# gpxtendo.net
KiCad netlist of a schematic drawn in EAGLE
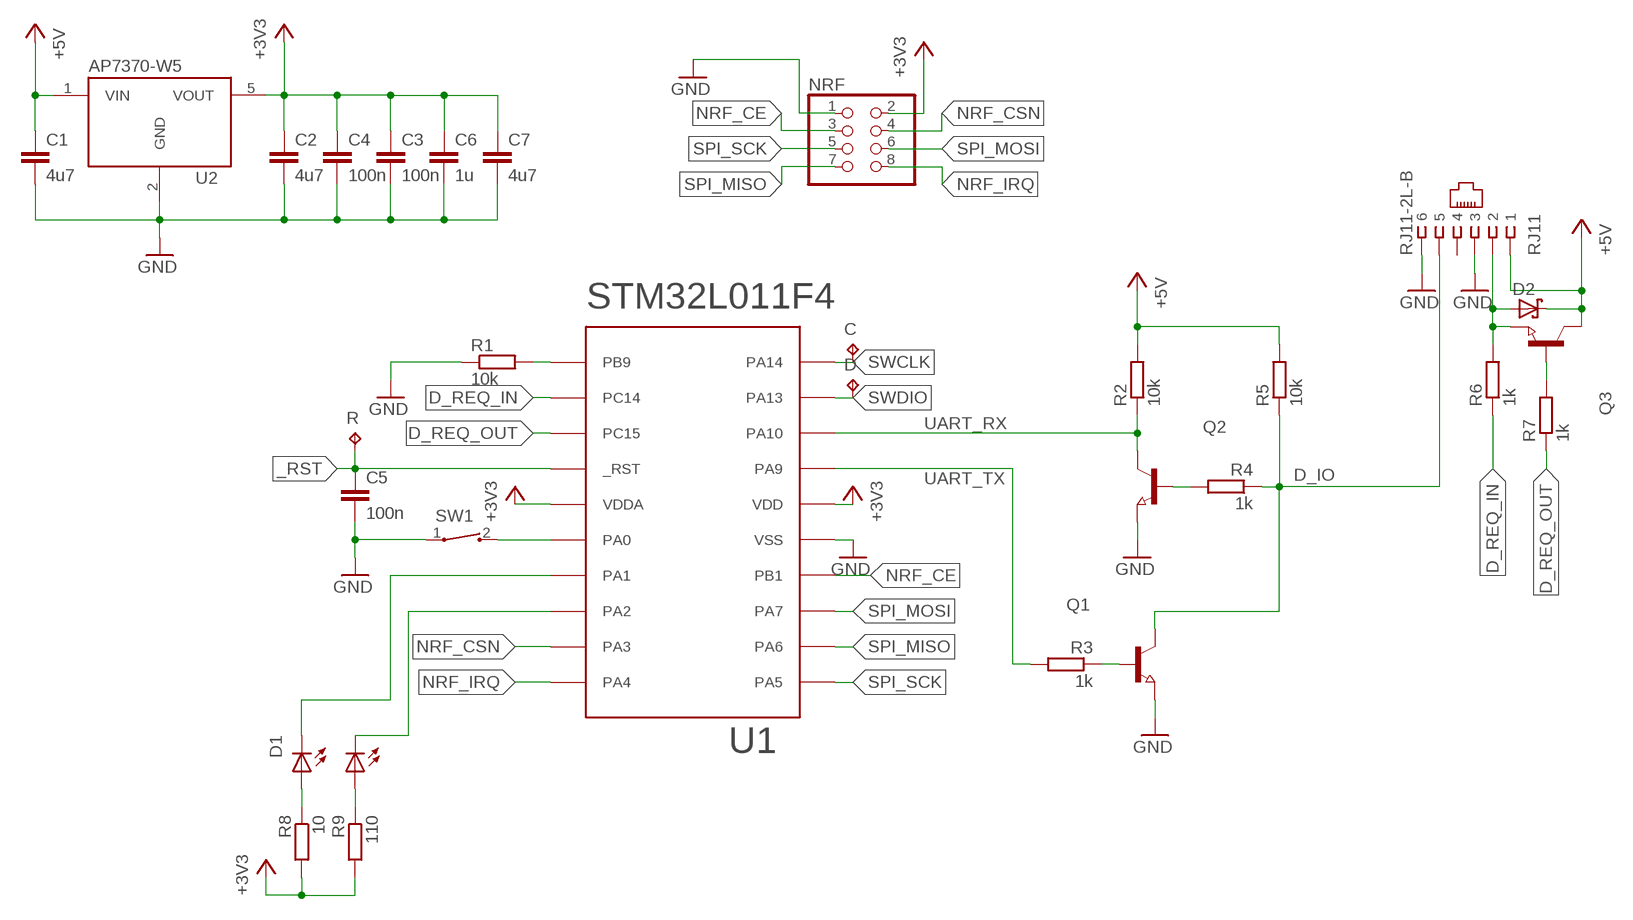
[diagram p0: schematic, sheet 1]

(export (version "E")
  (design (tool "Eeschema 10.0.6"))
  (components
    (comp (ref "C")
      (value "TPTP10R")
      (footprint "eagle-import:TP10R")
      (libsource (lib "eagle-import") (part "TPTP10R"))
    )
    (comp (ref "C1")
      (value "4u7")
      (footprint "eagle-import:C0603-S")
      (libsource (lib "eagle-import") (part "C0603-S"))
    )
    (comp (ref "C2")
      (value "4u7")
      (footprint "eagle-import:C0603-S")
      (libsource (lib "eagle-import") (part "C0603-S"))
    )
    (comp (ref "C3")
      (value "100n")
      (footprint "eagle-import:C0603-S")
      (libsource (lib "eagle-import") (part "C0603-S"))
    )
    (comp (ref "C4")
      (value "100n")
      (footprint "eagle-import:C0603-S")
      (libsource (lib "eagle-import") (part "C0603-S"))
    )
    (comp (ref "C5")
      (value "100n")
      (footprint "eagle-import:C0603-S")
      (libsource (lib "eagle-import") (part "C0603-S"))
    )
    (comp (ref "C6")
      (value "1u")
      (footprint "eagle-import:C0603-S")
      (libsource (lib "eagle-import") (part "C0603-S"))
    )
    (comp (ref "C7")
      (value "4u7")
      (footprint "eagle-import:C0603-S")
      (libsource (lib "eagle-import") (part "C0603-S"))
    )
    (comp (ref "D")
      (value "TPTP10R")
      (footprint "eagle-import:TP10R")
      (libsource (lib "eagle-import") (part "TPTP10R"))
    )
    (comp (ref "D1")
      (value "LED-DUAL")
      (footprint "eagle-import:LED-1210")
      (libsource (lib "eagle-import") (part "LED-DUAL"))
    )
    (comp (ref "D2")
      (value "PMEG4030")
      (footprint "eagle-import:SOD123")
      (libsource (lib "eagle-import") (part "PMEG4030"))
    )
    (comp (ref "NRF")
      (value "PINHD-2X4")
      (footprint "eagle-import:2X04")
      (libsource (lib "eagle-import") (part "PINHD-2X4"))
    )
    (comp (ref "Q1")
      (value "NPN-TRANSISTOR_SOT23")
      (footprint "eagle-import:SOT23")
      (libsource (lib "eagle-import") (part "NPN-TRANSISTOR_SOT23"))
    )
    (comp (ref "Q2")
      (value "NPN-TRANSISTOR_SOT23")
      (footprint "eagle-import:SOT23")
      (libsource (lib "eagle-import") (part "NPN-TRANSISTOR_SOT23"))
    )
    (comp (ref "Q3")
      (value "NPN-TRANSISTOR_SOT23")
      (footprint "eagle-import:SOT23")
      (libsource (lib "eagle-import") (part "NPN-TRANSISTOR_SOT23"))
    )
    (comp (ref "R")
      (value "TPTP10R")
      (footprint "eagle-import:TP10R")
      (libsource (lib "eagle-import") (part "TPTP10R"))
    )
    (comp (ref "R1")
      (value "10k")
      (footprint "eagle-import:R0603-S")
      (libsource (lib "eagle-import") (part "R0603-S"))
    )
    (comp (ref "R2")
      (value "10k")
      (footprint "eagle-import:R0603-S")
      (libsource (lib "eagle-import") (part "R0603-S"))
    )
    (comp (ref "R3")
      (value "1k")
      (footprint "eagle-import:R0603-S")
      (libsource (lib "eagle-import") (part "R0603-S"))
    )
    (comp (ref "R4")
      (value "1k")
      (footprint "eagle-import:R0603-S")
      (libsource (lib "eagle-import") (part "R0603-S"))
    )
    (comp (ref "R5")
      (value "10k")
      (footprint "eagle-import:R0603-S")
      (libsource (lib "eagle-import") (part "R0603-S"))
    )
    (comp (ref "R6")
      (value "1k")
      (footprint "eagle-import:R0603-S")
      (libsource (lib "eagle-import") (part "R0603-S"))
    )
    (comp (ref "R7")
      (value "1k")
      (footprint "eagle-import:R0603-S")
      (libsource (lib "eagle-import") (part "R0603-S"))
    )
    (comp (ref "R8")
      (value "10")
      (footprint "eagle-import:R0603-S")
      (libsource (lib "eagle-import") (part "R0603-S"))
    )
    (comp (ref "R9")
      (value "110")
      (footprint "eagle-import:R0603-S")
      (libsource (lib "eagle-import") (part "R0603-S"))
    )
    (comp (ref "RJ11")
      (value "RJ11-2L-B")
      (footprint "eagle-import:RJ11-NO_SHIELD")
      (fields (field (name "MF") "TYCO ELECTRONICS"))
      (libsource (lib "eagle-import") (part "RJ11-2L-B"))
    )
    (comp (ref "SW1")
      (value "SW-SPST")
      (footprint "eagle-import:TL3330")
      (libsource (lib "eagle-import") (part "SW-SPST"))
    )
    (comp (ref "U1")
      (value "STM32L011F4PX")
      (footprint "eagle-import:TSSOP-20")
      (libsource (lib "eagle-import") (part "STM32L011F4PX"))
    )
    (comp (ref "U2")
      (value "AP7370-W5")
      (footprint "eagle-import:SOT23-5")
      (libsource (lib "eagle-import") (part "AP7370-W5"))
    )
  )
  (nets
    (net (code "1") (name "+3V3") (class "Default")
      (node (ref "C2") (pin "1") (pinfunction "1_1") (pintype "passive"))
      (node (ref "C3") (pin "1") (pinfunction "1_1") (pintype "passive"))
      (node (ref "C4") (pin "1") (pinfunction "1_1") (pintype "passive"))
      (node (ref "C6") (pin "1") (pinfunction "1_1") (pintype "passive"))
      (node (ref "C7") (pin "1") (pinfunction "1_1") (pintype "passive"))
      (node (ref "NRF") (pin "2") (pinfunction "2_2") (pintype "passive"))
      (node (ref "R8") (pin "2") (pinfunction "2_2") (pintype "passive"))
      (node (ref "R9") (pin "2") (pinfunction "2_2") (pintype "passive"))
      (node (ref "U1") (pin "P$16") (pinfunction "VDD_P$16") (pintype "power_in"))
      (node (ref "U1") (pin "P$5") (pinfunction "VDDA_P$5") (pintype "power_in"))
      (node (ref "U2") (pin "5") (pinfunction "VOUT_5") (pintype "bidirectional"))
    )
    (net (code "2") (name "+5V") (class "Default")
      (node (ref "C1") (pin "1") (pinfunction "1_1") (pintype "passive"))
      (node (ref "D2") (pin "C") (pinfunction "C_C") (pintype "passive"))
      (node (ref "Q3") (pin "3") (pinfunction "C_3") (pintype "passive"))
      (node (ref "R2") (pin "2") (pinfunction "2_2") (pintype "passive"))
      (node (ref "R5") (pin "2") (pinfunction "2_2") (pintype "passive"))
      (node (ref "RJ11") (pin "1") (pinfunction "1_1") (pintype "passive"))
      (node (ref "U2") (pin "1") (pinfunction "VIN_1") (pintype "bidirectional"))
    )
    (net (code "3") (name "/D_IO") (class "Default")
      (node (ref "Q1") (pin "3") (pinfunction "C_3") (pintype "passive"))
      (node (ref "R4") (pin "1") (pinfunction "1_1") (pintype "passive"))
      (node (ref "R5") (pin "1") (pinfunction "1_1") (pintype "passive"))
      (node (ref "RJ11") (pin "5") (pinfunction "5_5") (pintype "passive"))
    )
    (net (code "4") (name "/UART_RX") (class "Default")
      (node (ref "Q2") (pin "3") (pinfunction "C_3") (pintype "passive"))
      (node (ref "R2") (pin "1") (pinfunction "1_1") (pintype "passive"))
      (node (ref "U1") (pin "P$18") (pinfunction "PA10_P$18") (pintype "bidirectional"))
    )
    (net (code "5") (name "/UART_TX") (class "Default")
      (node (ref "R3") (pin "2") (pinfunction "2_2") (pintype "passive"))
      (node (ref "U1") (pin "P$17") (pinfunction "PA9_P$17") (pintype "bidirectional"))
    )
    (net (code "6") (name "D_REQ_IN") (class "Default")
      (node (ref "R6") (pin "1") (pinfunction "1_1") (pintype "passive"))
      (node (ref "U1") (pin "P$2") (pinfunction "PC14_P$2") (pintype "bidirectional"))
    )
    (net (code "7") (name "D_REQ_OUT") (class "Default")
      (node (ref "R7") (pin "1") (pinfunction "1_1") (pintype "passive"))
      (node (ref "U1") (pin "P$3") (pinfunction "PC15_P$3") (pintype "bidirectional"))
    )
    (net (code "8") (name "GND") (class "Default")
      (node (ref "C1") (pin "2") (pinfunction "2_2") (pintype "passive"))
      (node (ref "C2") (pin "2") (pinfunction "2_2") (pintype "passive"))
      (node (ref "C3") (pin "2") (pinfunction "2_2") (pintype "passive"))
      (node (ref "C4") (pin "2") (pinfunction "2_2") (pintype "passive"))
      (node (ref "C5") (pin "2") (pinfunction "2_2") (pintype "passive"))
      (node (ref "C6") (pin "2") (pinfunction "2_2") (pintype "passive"))
      (node (ref "C7") (pin "2") (pinfunction "2_2") (pintype "passive"))
      (node (ref "NRF") (pin "1") (pinfunction "1_1") (pintype "passive"))
      (node (ref "Q1") (pin "2") (pinfunction "E_2") (pintype "passive"))
      (node (ref "Q2") (pin "2") (pinfunction "E_2") (pintype "passive"))
      (node (ref "R1") (pin "1") (pinfunction "1_1") (pintype "passive"))
      (node (ref "RJ11") (pin "3") (pinfunction "3_3") (pintype "passive"))
      (node (ref "RJ11") (pin "6") (pinfunction "6_6") (pintype "passive"))
      (node (ref "SW1") (pin "1") (pinfunction "1_1") (pintype "passive"))
      (node (ref "U1") (pin "P$15") (pinfunction "VSS_P$15") (pintype "power_in"))
      (node (ref "U2") (pin "2") (pinfunction "GND_2") (pintype "bidirectional"))
    )
    (net (code "9") (name "NRF_CE") (class "Default")
      (node (ref "NRF") (pin "3") (pinfunction "3_3") (pintype "passive"))
      (node (ref "U1") (pin "P$14") (pinfunction "PB1_P$14") (pintype "bidirectional"))
    )
    (net (code "10") (name "NRF_CSN") (class "Default")
      (node (ref "NRF") (pin "4") (pinfunction "4_4") (pintype "passive"))
      (node (ref "U1") (pin "P$9") (pinfunction "PA3_P$9") (pintype "bidirectional"))
    )
    (net (code "11") (name "NRF_IRQ") (class "Default")
      (node (ref "NRF") (pin "8") (pinfunction "8_8") (pintype "passive"))
      (node (ref "U1") (pin "P$10") (pinfunction "PA4_P$10") (pintype "bidirectional"))
    )
    (net (code "12") (name "Net-(D1-A0)") (class "Default")
      (node (ref "D1") (pin "2") (pinfunction "A0_2") (pintype "passive"))
      (node (ref "R9") (pin "1") (pinfunction "1_1") (pintype "passive"))
    )
    (net (code "13") (name "Net-(D1-A1)") (class "Default")
      (node (ref "D1") (pin "4") (pinfunction "A1_4") (pintype "passive"))
      (node (ref "R8") (pin "1") (pinfunction "1_1") (pintype "passive"))
    )
    (net (code "14") (name "Net-(D1-C0)") (class "Default")
      (node (ref "D1") (pin "1") (pinfunction "C0_1") (pintype "passive"))
      (node (ref "U1") (pin "P$8") (pinfunction "PA2_P$8") (pintype "bidirectional"))
    )
    (net (code "15") (name "Net-(D1-C1)") (class "Default")
      (node (ref "D1") (pin "3") (pinfunction "C1_3") (pintype "passive"))
      (node (ref "U1") (pin "P$7") (pinfunction "PA1_P$7") (pintype "bidirectional"))
    )
    (net (code "16") (name "Net-(Q1-B)") (class "Default")
      (node (ref "Q1") (pin "1") (pinfunction "B_1") (pintype "passive"))
      (node (ref "R3") (pin "1") (pinfunction "1_1") (pintype "passive"))
    )
    (net (code "17") (name "Net-(Q2-B)") (class "Default")
      (node (ref "Q2") (pin "1") (pinfunction "B_1") (pintype "passive"))
      (node (ref "R4") (pin "2") (pinfunction "2_2") (pintype "passive"))
    )
    (net (code "18") (name "Net-(Q3-B)") (class "Default")
      (node (ref "Q3") (pin "1") (pinfunction "B_1") (pintype "passive"))
      (node (ref "R7") (pin "2") (pinfunction "2_2") (pintype "passive"))
    )
    (net (code "19") (name "Net-(Q3-E)") (class "Default")
      (node (ref "D2") (pin "A") (pinfunction "A_A") (pintype "passive"))
      (node (ref "Q3") (pin "2") (pinfunction "E_2") (pintype "passive"))
      (node (ref "R6") (pin "2") (pinfunction "2_2") (pintype "passive"))
      (node (ref "RJ11") (pin "2") (pinfunction "2_2") (pintype "passive"))
    )
    (net (code "20") (name "Net-(U1-PA0)") (class "Default")
      (node (ref "SW1") (pin "2") (pinfunction "2_2") (pintype "passive"))
      (node (ref "U1") (pin "P$6") (pinfunction "PA0_P$6") (pintype "bidirectional"))
    )
    (net (code "21") (name "Net-(U1-PB9)") (class "Default")
      (node (ref "R1") (pin "2") (pinfunction "2_2") (pintype "passive"))
      (node (ref "U1") (pin "P$1") (pinfunction "PB9_P$1") (pintype "bidirectional"))
    )
    (net (code "22") (name "SPI_MISO") (class "Default")
      (node (ref "NRF") (pin "7") (pinfunction "7_7") (pintype "passive"))
      (node (ref "U1") (pin "P$12") (pinfunction "PA6_P$12") (pintype "bidirectional"))
    )
    (net (code "23") (name "SPI_MOSI") (class "Default")
      (node (ref "NRF") (pin "6") (pinfunction "6_6") (pintype "passive"))
      (node (ref "U1") (pin "P$13") (pinfunction "PA7_P$13") (pintype "bidirectional"))
    )
    (net (code "24") (name "SPI_SCK") (class "Default")
      (node (ref "NRF") (pin "5") (pinfunction "5_5") (pintype "passive"))
      (node (ref "U1") (pin "P$11") (pinfunction "PA5_P$11") (pintype "bidirectional"))
    )
    (net (code "25") (name "SWCLK") (class "Default")
      (node (ref "C") (pin "TP") (pinfunction "TP_TP") (pintype "input"))
      (node (ref "U1") (pin "P$20") (pinfunction "PA14_P$20") (pintype "bidirectional"))
    )
    (net (code "26") (name "SWDIO") (class "Default")
      (node (ref "D") (pin "TP") (pinfunction "TP_TP") (pintype "input"))
      (node (ref "U1") (pin "P$19") (pinfunction "PA13_P$19") (pintype "bidirectional"))
    )
    (net (code "27") (name "_RST") (class "Default")
      (node (ref "C5") (pin "1") (pinfunction "1_1") (pintype "passive"))
      (node (ref "R") (pin "TP") (pinfunction "TP_TP") (pintype "input"))
      (node (ref "U1") (pin "P$4") (pinfunction "_RST_P$4") (pintype "bidirectional"))
    )
    (net (code "28") (name "unconnected-(RJ11-Pad4)") (class "Default")
      (node (ref "RJ11") (pin "4") (pinfunction "4_4") (pintype "passive"))
    )
  )
)
